# YOTSUBA_GNSS-receiver_Orion_ver_1_5_3.net
KiCad netlist of a schematic drawn in EAGLE
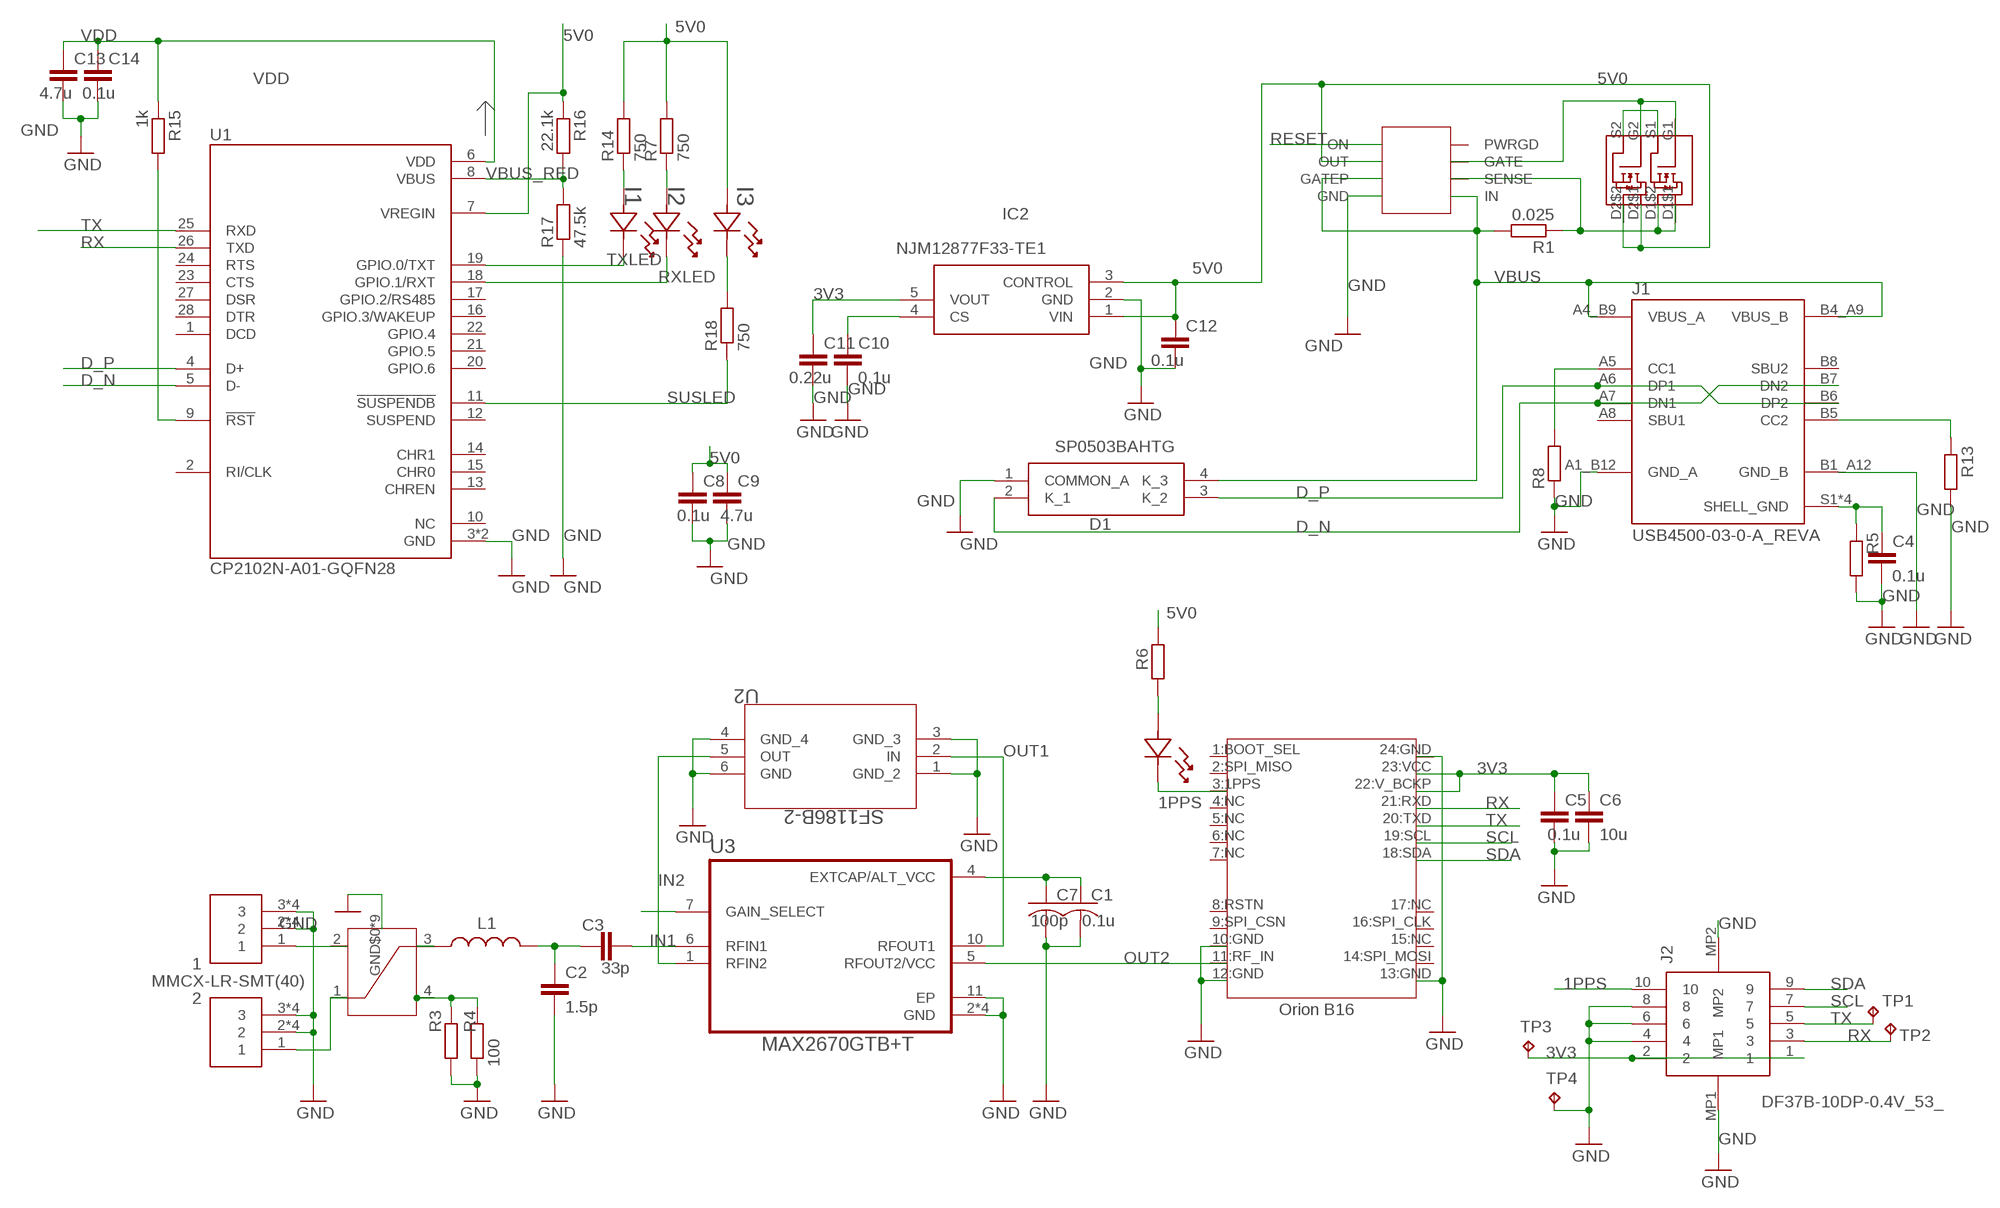
[diagram p0: schematic, sheet 1]

(export (version "E")
  (design (tool "Eeschema 10.0.6"))
  (components
    (comp (ref "1")
      (value "MMCX-LR-SMT(40)")
      (footprint "eagle-import:MMCX-LR-SMT(40)")
      (libsource (lib "eagle-import") (part "MMCX-LR-SMT(40)"))
    )
    (comp (ref "2")
      (value "MMCX-LR-SMT(40)")
      (footprint "eagle-import:MMCX-LR-SMT(40)")
      (libsource (lib "eagle-import") (part "MMCX-LR-SMT(40)"))
    )
    (comp (ref "C1")
      (value "0.1u")
      (footprint "eagle-import:C1608_OS")
      (libsource (lib "eagle-import") (part "C-US"))
    )
    (comp (ref "C2")
      (value "1.5p")
      (footprint "eagle-import:C1608")
      (libsource (lib "eagle-import") (part "C-EUC1608"))
    )
    (comp (ref "C3")
      (value "33p")
      (footprint "eagle-import:C1608")
      (libsource (lib "eagle-import") (part "C-EUC1608"))
    )
    (comp (ref "C4")
      (value "0.1u")
      (footprint "eagle-import:C1608")
      (libsource (lib "eagle-import") (part "C-EUC1608"))
    )
    (comp (ref "C5")
      (value "0.1u")
      (footprint "eagle-import:C1608")
      (libsource (lib "eagle-import") (part "C-EUC1608"))
    )
    (comp (ref "C6")
      (value "10u")
      (footprint "eagle-import:C1608")
      (libsource (lib "eagle-import") (part "C-EUC1608"))
    )
    (comp (ref "C7")
      (value "100p")
      (footprint "eagle-import:C1608_OS")
      (libsource (lib "eagle-import") (part "C-US"))
    )
    (comp (ref "C8")
      (value "0.1u")
      (footprint "eagle-import:C1608")
      (libsource (lib "eagle-import") (part "C-EUC1608"))
    )
    (comp (ref "C9")
      (value "4.7u")
      (footprint "eagle-import:C1608")
      (libsource (lib "eagle-import") (part "C-EUC1608"))
    )
    (comp (ref "C10")
      (value "0.1u")
      (footprint "eagle-import:C1608")
      (libsource (lib "eagle-import") (part "C-EUC1608"))
    )
    (comp (ref "C11")
      (value "0.22u")
      (footprint "eagle-import:C1608")
      (libsource (lib "eagle-import") (part "C-EUC1608"))
    )
    (comp (ref "C12")
      (value "0.1u")
      (footprint "eagle-import:C1608")
      (libsource (lib "eagle-import") (part "C-EUC1608"))
    )
    (comp (ref "C13")
      (value "4.7u")
      (footprint "eagle-import:C1608")
      (libsource (lib "eagle-import") (part "C-EUC1608"))
    )
    (comp (ref "C14")
      (value "0.1u")
      (footprint "eagle-import:C1608")
      (libsource (lib "eagle-import") (part "C-EUC1608"))
    )
    (comp (ref "D1")
      (value "SP0503BAHTG")
      (footprint "eagle-import:SP0503BAHTG")
      (fields (field (name "MOUSER_PART_NUMBER") "576-SP0503BAHTG"))
      (libsource (lib "eagle-import") (part "SP0503BAHTG"))
    )
    (comp (ref "I1")
      (value "SML-E12P8WT86")
      (footprint "eagle-import:LED_SMLD12_ROM")
      (fields (field (name "COPYRIGHT") "Copyright (C) 2023 Ultra Librarian. All rights reserved."))
      (libsource (lib "eagle-import") (part "SML-E12P8WT86"))
    )
    (comp (ref "I2")
      (value "SML-E12P8WT86")
      (footprint "eagle-import:LED_SMLD12_ROM")
      (fields (field (name "COPYRIGHT") "Copyright (C) 2023 Ultra Librarian. All rights reserved."))
      (libsource (lib "eagle-import") (part "SML-E12P8WT86"))
    )
    (comp (ref "I3")
      (value "SML-E12P8WT86")
      (footprint "eagle-import:LED_SMLD12_ROM")
      (fields (field (name "COPYRIGHT") "Copyright (C) 2023 Ultra Librarian. All rights reserved."))
      (libsource (lib "eagle-import") (part "SML-E12P8WT86"))
    )
    (comp (ref "IC2")
      (value "NJM12877F33-TE1")
      (footprint "eagle-import:SOT95P280X120-5N")
      (fields (field (name "MOUSER_PART_NUMBER") "513-NJM12877F33-TE1"))
      (libsource (lib "eagle-import") (part "NJM12877F33-TE1"))
    )
    (comp (ref "J1")
      (value "USB4500-03-0-A_REVA")
      (footprint "eagle-import:GCT_USB4500-03-0-A_REVA")
      (fields
        (field (name "DIGI-KEY_PART_NUMBER") "2073-USB4500-03-0-ATR-ND")
        (field (name "MF") "Global Connector Technology")
        (field (name "MP") "USB4500-03-0-A")
      )
      (libsource (lib "eagle-import") (part "USB4500-03-0-A_REVA"))
    )
    (comp (ref "J2")
      (value "DF37B-10DP-0.4V_53_")
      (footprint "eagle-import:DF37B10DP04V53")
      (fields
        (field (name "MANUFACTURER_PART_NUMBER") "DF37B-10DP-0.4V(53)")
        (field (name "MOUSER_PART_NUMBER") "798-DF37B10DP04V53")
      )
      (libsource (lib "eagle-import") (part "DF37B-10DP-0.4V_53_"))
    )
    (comp (ref "L1")
      (value "4.3n")
      (footprint "eagle-import:INDC1608X100N")
      (fields
        (field (name "DIGIKEY_PART_NUMBER") "490-6896-2-ND")
        (field (name "MF") "Murata")
        (field (name "MP") "LQW18AN4N3C00D")
      )
      (libsource (lib "eagle-import") (part "LQW18AN4N3C00D"))
    )
    (comp (ref "R1")
      (value "0.025")
      (footprint "eagle-import:R0603")
      (libsource (lib "eagle-import") (part "R-EU_R0603"))
    )
    (comp (ref "R3")
      (value "100")
      (footprint "eagle-import:R0603")
      (libsource (lib "eagle-import") (part "R-EU_R0603"))
    )
    (comp (ref "R4")
      (value "100")
      (footprint "eagle-import:R0603")
      (libsource (lib "eagle-import") (part "R-EU_R0603"))
    )
    (comp (ref "R5")
      (value "R-EU_R0603")
      (footprint "eagle-import:R0603")
      (libsource (lib "eagle-import") (part "R-EU_R0603"))
    )
    (comp (ref "R6")
      (value "R-EU_R0603")
      (footprint "eagle-import:R0603")
      (libsource (lib "eagle-import") (part "R-EU_R0603"))
    )
    (comp (ref "R7")
      (value "750")
      (footprint "eagle-import:R0603")
      (libsource (lib "eagle-import") (part "R-EU_R0603"))
    )
    (comp (ref "R8")
      (value "R-EU_R0603")
      (footprint "eagle-import:R0603")
      (libsource (lib "eagle-import") (part "R-EU_R0603"))
    )
    (comp (ref "R10")
      (value "SML-E12P8WT86")
      (footprint "eagle-import:LED_SMLD12_ROM")
      (fields (field (name "COPYRIGHT") "Copyright (C) 2023 Ultra Librarian. All rights reserved."))
      (libsource (lib "eagle-import") (part "SML-E12P8WT86"))
    )
    (comp (ref "R13")
      (value "R-EU_R0603")
      (footprint "eagle-import:R0603")
      (libsource (lib "eagle-import") (part "R-EU_R0603"))
    )
    (comp (ref "R14")
      (value "750")
      (footprint "eagle-import:R0603")
      (libsource (lib "eagle-import") (part "R-EU_R0603"))
    )
    (comp (ref "R15")
      (value "1k")
      (footprint "eagle-import:R0603")
      (libsource (lib "eagle-import") (part "R-EU_R0603"))
    )
    (comp (ref "R16")
      (value "22.1k")
      (footprint "eagle-import:R0603")
      (libsource (lib "eagle-import") (part "R-EU_R0603"))
    )
    (comp (ref "R17")
      (value "47.5k")
      (footprint "eagle-import:R0603")
      (libsource (lib "eagle-import") (part "R-EU_R0603"))
    )
    (comp (ref "R18")
      (value "750")
      (footprint "eagle-import:R0603")
      (libsource (lib "eagle-import") (part "R-EU_R0603"))
    )
    (comp (ref "TP1")
      (value "TPTP13SQ")
      (footprint "eagle-import:TP13SQ")
      (libsource (lib "eagle-import") (part "TPTP13SQ"))
    )
    (comp (ref "TP2")
      (value "TPTP13SQ")
      (footprint "eagle-import:TP13SQ")
      (libsource (lib "eagle-import") (part "TPTP13SQ"))
    )
    (comp (ref "TP3")
      (value "TPTP13SQ")
      (footprint "eagle-import:TP13SQ")
      (libsource (lib "eagle-import") (part "TPTP13SQ"))
    )
    (comp (ref "TP4")
      (value "TPTP13SQ")
      (footprint "eagle-import:TP13SQ")
      (libsource (lib "eagle-import") (part "TPTP13SQ"))
    )
    (comp (ref "U$1")
      (value "ORION_B16")
      (footprint "eagle-import:ORION_B16")
      (libsource (lib "eagle-import") (part "ORION_B16"))
    )
    (comp (ref "U$3")
      (value "HC125.A")
      (footprint "eagle-import:HC125.A")
      (libsource (lib "eagle-import") (part "HC125.A"))
    )
    (comp (ref "U$7")
      (value "DMG6898LSD")
      (footprint "eagle-import:SOIC127P600X150-8N")
      (libsource (lib "eagle-import") (part "DMG6898LSD"))
    )
    (comp (ref "U$8")
      (value "LTC4361")
      (footprint "eagle-import:SOP65P280X100-8N")
      (libsource (lib "eagle-import") (part "LTC4361"))
    )
    (comp (ref "U1")
      (value "CP2102N-A01-GQFN28")
      (footprint "eagle-import:QFN50P500X500X80-29N")
      (fields (field (name "MF") "Silicon Labs"))
      (libsource (lib "eagle-import") (part "CP2102N-A01-GQFN28"))
    )
    (comp (ref "U2")
      (value "SF1186B-2")
      (footprint "eagle-import:SM3030_MUR")
      (fields (field (name "COPYRIGHT") "Copyright (C) 2023 Ultra Librarian. All rights reserved."))
      (libsource (lib "eagle-import") (part "SF1186B-2"))
    )
    (comp (ref "U3")
      (value "MAX2670GTB+T")
      (footprint "eagle-import:DFN300X300X80-11N")
      (fields (field (name "MF") "Analog Devices"))
      (libsource (lib "eagle-import") (part "MAX2670GTB+T"))
    )
  )
  (nets
    (net (code "1") (name "/1PPS") (class "Default")
      (node (ref "J2") (pin "10") (pinfunction "10_10") (pintype "bidirectional"))
      (node (ref "R10") (pin "1") (pinfunction "1_1") (pintype "passive"))
      (node (ref "U$1") (pin "3:1PPS") (pinfunction "3:1PPS_3:1PPS") (pintype "bidirectional"))
    )
    (net (code "2") (name "/3V3") (class "Default")
      (node (ref "C11") (pin "1") (pinfunction "1_1") (pintype "passive"))
      (node (ref "C5") (pin "1") (pinfunction "1_1") (pintype "passive"))
      (node (ref "C6") (pin "1") (pinfunction "1_1") (pintype "passive"))
      (node (ref "IC2") (pin "5") (pinfunction "VOUT_5") (pintype "bidirectional"))
      (node (ref "J2") (pin "1") (pinfunction "1_1") (pintype "bidirectional"))
      (node (ref "J2") (pin "2") (pinfunction "2_2") (pintype "bidirectional"))
      (node (ref "TP3") (pin "TP") (pinfunction "TP_TP") (pintype "input"))
      (node (ref "U$1") (pin "22:V_BCKP") (pinfunction "22:V_BCKP_22:V_BCKP") (pintype "bidirectional"))
      (node (ref "U$1") (pin "23:VCC") (pinfunction "23:VCC_23:VCC") (pintype "bidirectional"))
    )
    (net (code "3") (name "/5V0") (class "Default")
      (node (ref "C12") (pin "1") (pinfunction "1_1") (pintype "passive"))
      (node (ref "C8") (pin "1") (pinfunction "1_1") (pintype "passive"))
      (node (ref "C9") (pin "1") (pinfunction "1_1") (pintype "passive"))
      (node (ref "I3") (pin "2") (pinfunction "2_2") (pintype "passive"))
      (node (ref "IC2") (pin "1") (pinfunction "VIN_1") (pintype "bidirectional"))
      (node (ref "IC2") (pin "3") (pinfunction "CONTROL_3") (pintype "bidirectional"))
      (node (ref "R14") (pin "2") (pinfunction "2_2") (pintype "passive"))
      (node (ref "R16") (pin "1") (pinfunction "1_1") (pintype "passive"))
      (node (ref "R6") (pin "2") (pinfunction "2_2") (pintype "passive"))
      (node (ref "R7") (pin "2") (pinfunction "2_2") (pintype "passive"))
      (node (ref "U$7") (pin "D2$1") (pinfunction "D2$1_D2$1") (pintype "bidirectional"))
      (node (ref "U$7") (pin "D2$2") (pinfunction "D2$2_D2$2") (pintype "bidirectional"))
      (node (ref "U$8") (pin "OUT") (pinfunction "OUT_OUT") (pintype "bidirectional"))
      (node (ref "U1") (pin "7") (pinfunction "VREGIN_7") (pintype "power_in"))
    )
    (net (code "4") (name "/D_N") (class "Default")
      (node (ref "D1") (pin "2") (pinfunction "K_1_2") (pintype "bidirectional"))
      (node (ref "J1") (pin "A7") (pinfunction "DN1_A7") (pintype "bidirectional"))
      (node (ref "J1") (pin "B7") (pinfunction "DN2_B7") (pintype "bidirectional"))
      (node (ref "U1") (pin "5") (pinfunction "D-_5") (pintype "bidirectional"))
    )
    (net (code "5") (name "/D_P") (class "Default")
      (node (ref "D1") (pin "3") (pinfunction "K_2_3") (pintype "bidirectional"))
      (node (ref "J1") (pin "A6") (pinfunction "DP1_A6") (pintype "bidirectional"))
      (node (ref "J1") (pin "B6") (pinfunction "DP2_B6") (pintype "bidirectional"))
      (node (ref "U1") (pin "4") (pinfunction "D+_4") (pintype "bidirectional"))
    )
    (net (code "6") (name "/IN1") (class "Default")
      (node (ref "C3") (pin "2") (pinfunction "2_2") (pintype "passive"))
      (node (ref "U3") (pin "6") (pinfunction "RFIN1_6") (pintype "input"))
    )
    (net (code "7") (name "/IN2") (class "Default")
      (node (ref "U2") (pin "5") (pinfunction "OUT_5") (pintype "output"))
      (node (ref "U3") (pin "1") (pinfunction "RFIN2_1") (pintype "input"))
    )
    (net (code "8") (name "/OUT1") (class "Default")
      (node (ref "U2") (pin "2") (pinfunction "IN_2") (pintype "input"))
      (node (ref "U3") (pin "10") (pinfunction "RFOUT1_10") (pintype "output"))
    )
    (net (code "9") (name "/OUT2") (class "Default")
      (node (ref "U$1") (pin "11:RF_IN") (pinfunction "11:RF_IN_11:RF_IN") (pintype "bidirectional"))
      (node (ref "U3") (pin "5") (pinfunction "RFOUT2/VCC_5") (pintype "output"))
    )
    (net (code "10") (name "/RESET") (class "Default")
      (node (ref "U$8") (pin "ON") (pinfunction "ON_ON") (pintype "bidirectional"))
    )
    (net (code "11") (name "/RX") (class "Default")
      (node (ref "J2") (pin "3") (pinfunction "3_3") (pintype "bidirectional"))
      (node (ref "TP2") (pin "TP") (pinfunction "TP_TP") (pintype "input"))
      (node (ref "U$1") (pin "21:RXD") (pinfunction "21:RXD_21:RXD") (pintype "bidirectional"))
      (node (ref "U1") (pin "26") (pinfunction "TXD_26") (pintype "output"))
    )
    (net (code "12") (name "/RXLED") (class "Default")
      (node (ref "I2") (pin "1") (pinfunction "1_1") (pintype "passive"))
      (node (ref "U1") (pin "18") (pinfunction "GPIO.1/RXT_18") (pintype "bidirectional"))
    )
    (net (code "13") (name "/SCL") (class "Default")
      (node (ref "J2") (pin "7") (pinfunction "7_7") (pintype "bidirectional"))
      (node (ref "U$1") (pin "19:SCL") (pinfunction "19:SCL_19:SCL") (pintype "bidirectional"))
    )
    (net (code "14") (name "/SDA") (class "Default")
      (node (ref "J2") (pin "9") (pinfunction "9_9") (pintype "bidirectional"))
      (node (ref "U$1") (pin "18:SDA") (pinfunction "18:SDA_18:SDA") (pintype "bidirectional"))
    )
    (net (code "15") (name "/SUSLED") (class "Default")
      (node (ref "R18") (pin "1") (pinfunction "1_1") (pintype "passive"))
      (node (ref "U1") (pin "11") (pinfunction "~{SUSPENDB}_11") (pintype "output"))
    )
    (net (code "16") (name "/TX") (class "Default")
      (node (ref "J2") (pin "5") (pinfunction "5_5") (pintype "bidirectional"))
      (node (ref "TP1") (pin "TP") (pinfunction "TP_TP") (pintype "input"))
      (node (ref "U$1") (pin "20:TXD") (pinfunction "20:TXD_20:TXD") (pintype "bidirectional"))
      (node (ref "U1") (pin "25") (pinfunction "RXD_25") (pintype "input"))
    )
    (net (code "17") (name "/TXLED") (class "Default")
      (node (ref "I1") (pin "1") (pinfunction "1_1") (pintype "passive"))
      (node (ref "U1") (pin "19") (pinfunction "GPIO.0/TXT_19") (pintype "bidirectional"))
    )
    (net (code "18") (name "/VBUS") (class "Default")
      (node (ref "D1") (pin "4") (pinfunction "K_3_4") (pintype "bidirectional"))
      (node (ref "J1") (pin "A4_B9") (pinfunction "VBUS_A_A4_B9") (pintype "power_in"))
      (node (ref "J1") (pin "B4_A9") (pinfunction "VBUS_B_B4_A9") (pintype "power_in"))
      (node (ref "R1") (pin "2") (pinfunction "2_2") (pintype "passive"))
      (node (ref "U$8") (pin "GATEP") (pinfunction "GATEP_GATEP") (pintype "bidirectional"))
      (node (ref "U$8") (pin "IN") (pinfunction "IN_IN") (pintype "bidirectional"))
    )
    (net (code "19") (name "/VBUS_RED") (class "Default")
      (node (ref "R16") (pin "2") (pinfunction "2_2") (pintype "passive"))
      (node (ref "R17") (pin "2") (pinfunction "2_2") (pintype "passive"))
      (node (ref "U1") (pin "8") (pinfunction "VBUS_8") (pintype "power_in"))
    )
    (net (code "20") (name "/VDD") (class "Default")
      (node (ref "C13") (pin "1") (pinfunction "1_1") (pintype "passive"))
      (node (ref "C14") (pin "1") (pinfunction "1_1") (pintype "passive"))
      (node (ref "R15") (pin "1") (pinfunction "1_1") (pintype "passive"))
      (node (ref "U1") (pin "6") (pinfunction "VDD_6") (pintype "power_in"))
    )
    (net (code "21") (name "GND") (class "Default")
      (node (ref "1") (pin "2") (pinfunction "2_2") (pintype "bidirectional"))
      (node (ref "1") (pin "3") (pinfunction "3_3") (pintype "bidirectional"))
      (node (ref "1") (pin "4") (pinfunction "2_4") (pintype "bidirectional"))
      (node (ref "1") (pin "5") (pinfunction "3_5") (pintype "bidirectional"))
      (node (ref "1") (pin "P$1") (pinfunction "2_P$1") (pintype "bidirectional"))
      (node (ref "1") (pin "P$2") (pinfunction "2_P$2") (pintype "bidirectional"))
      (node (ref "1") (pin "P$3") (pinfunction "3_P$3") (pintype "bidirectional"))
      (node (ref "1") (pin "P$4") (pinfunction "3_P$4") (pintype "bidirectional"))
      (node (ref "2") (pin "2") (pinfunction "2_2") (pintype "bidirectional"))
      (node (ref "2") (pin "3") (pinfunction "3_3") (pintype "bidirectional"))
      (node (ref "2") (pin "4") (pinfunction "2_4") (pintype "bidirectional"))
      (node (ref "2") (pin "5") (pinfunction "3_5") (pintype "bidirectional"))
      (node (ref "2") (pin "P$1") (pinfunction "2_P$1") (pintype "bidirectional"))
      (node (ref "2") (pin "P$2") (pinfunction "2_P$2") (pintype "bidirectional"))
      (node (ref "2") (pin "P$3") (pinfunction "3_P$3") (pintype "bidirectional"))
      (node (ref "2") (pin "P$4") (pinfunction "3_P$4") (pintype "bidirectional"))
      (node (ref "C1") (pin "2") (pinfunction "2_2") (pintype "passive"))
      (node (ref "C10") (pin "2") (pinfunction "2_2") (pintype "passive"))
      (node (ref "C11") (pin "2") (pinfunction "2_2") (pintype "passive"))
      (node (ref "C12") (pin "2") (pinfunction "2_2") (pintype "passive"))
      (node (ref "C13") (pin "2") (pinfunction "2_2") (pintype "passive"))
      (node (ref "C14") (pin "2") (pinfunction "2_2") (pintype "passive"))
      (node (ref "C2") (pin "2") (pinfunction "2_2") (pintype "passive"))
      (node (ref "C4") (pin "2") (pinfunction "2_2") (pintype "passive"))
      (node (ref "C5") (pin "2") (pinfunction "2_2") (pintype "passive"))
      (node (ref "C6") (pin "2") (pinfunction "2_2") (pintype "passive"))
      (node (ref "C7") (pin "2") (pinfunction "2_2") (pintype "passive"))
      (node (ref "C8") (pin "2") (pinfunction "2_2") (pintype "passive"))
      (node (ref "C9") (pin "2") (pinfunction "2_2") (pintype "passive"))
      (node (ref "D1") (pin "1") (pinfunction "COMMON_A_1") (pintype "bidirectional"))
      (node (ref "IC2") (pin "2") (pinfunction "GND_2") (pintype "bidirectional"))
      (node (ref "J1") (pin "A1_B12") (pinfunction "GND_A_A1_B12") (pintype "power_in"))
      (node (ref "J1") (pin "B1_A12") (pinfunction "GND_B_B1_A12") (pintype "power_in"))
      (node (ref "J2") (pin "4") (pinfunction "4_4") (pintype "bidirectional"))
      (node (ref "J2") (pin "6") (pinfunction "6_6") (pintype "bidirectional"))
      (node (ref "J2") (pin "8") (pinfunction "8_8") (pintype "bidirectional"))
      (node (ref "J2") (pin "MP1") (pinfunction "MP1_MP1") (pintype "bidirectional"))
      (node (ref "J2") (pin "MP2") (pinfunction "MP2_MP2") (pintype "bidirectional"))
      (node (ref "R13") (pin "2") (pinfunction "2_2") (pintype "passive"))
      (node (ref "R17") (pin "1") (pinfunction "1_1") (pintype "passive"))
      (node (ref "R3") (pin "1") (pinfunction "1_1") (pintype "passive"))
      (node (ref "R4") (pin "1") (pinfunction "1_1") (pintype "passive"))
      (node (ref "R5") (pin "2") (pinfunction "2_2") (pintype "passive"))
      (node (ref "R8") (pin "1") (pinfunction "1_1") (pintype "passive"))
      (node (ref "TP4") (pin "TP") (pinfunction "TP_TP") (pintype "input"))
      (node (ref "U$1") (pin "10:GND") (pinfunction "10:GND_10:GND") (pintype "bidirectional"))
      (node (ref "U$1") (pin "12:GND") (pinfunction "12:GND_12:GND") (pintype "bidirectional"))
      (node (ref "U$1") (pin "13:GND") (pinfunction "13:GND_13:GND") (pintype "bidirectional"))
      (node (ref "U$1") (pin "24:GND") (pinfunction "24:GND_24:GND") (pintype "bidirectional"))
      (node (ref "U$3") (pin "GND$0") (pinfunction "GND_GND$0") (pintype "bidirectional"))
      (node (ref "U$3") (pin "GND$1") (pinfunction "GND_GND$1") (pintype "bidirectional"))
      (node (ref "U$3") (pin "GND$2") (pinfunction "GND_GND$2") (pintype "bidirectional"))
      (node (ref "U$3") (pin "GND$3") (pinfunction "GND_GND$3") (pintype "bidirectional"))
      (node (ref "U$3") (pin "GND$4") (pinfunction "GND_GND$4") (pintype "bidirectional"))
      (node (ref "U$3") (pin "GND$5") (pinfunction "GND_GND$5") (pintype "bidirectional"))
      (node (ref "U$3") (pin "GND$6") (pinfunction "GND_GND$6") (pintype "bidirectional"))
      (node (ref "U$3") (pin "GND$7") (pinfunction "GND_GND$7") (pintype "bidirectional"))
      (node (ref "U$3") (pin "GND$8") (pinfunction "GND_GND$8") (pintype "bidirectional"))
      (node (ref "U$8") (pin "GND") (pinfunction "GND_GND") (pintype "bidirectional"))
      (node (ref "U1") (pin "29") (pinfunction "GND_29") (pintype "power_in"))
      (node (ref "U1") (pin "3") (pinfunction "GND_3") (pintype "power_in"))
      (node (ref "U2") (pin "1") (pinfunction "GND_2_1") (pintype "passive"))
      (node (ref "U2") (pin "3") (pinfunction "GND_3_3") (pintype "passive"))
      (node (ref "U2") (pin "4") (pinfunction "GND_4_4") (pintype "passive"))
      (node (ref "U2") (pin "6") (pinfunction "GND_6") (pintype "passive"))
      (node (ref "U3") (pin "11") (pinfunction "EP_11") (pintype "power_in"))
      (node (ref "U3") (pin "2") (pinfunction "GND_2") (pintype "power_in"))
      (node (ref "U3") (pin "3") (pinfunction "GND_3") (pintype "power_in"))
      (node (ref "U3") (pin "8") (pinfunction "GND_8") (pintype "power_in"))
      (node (ref "U3") (pin "9") (pinfunction "GND_9") (pintype "power_in"))
    )
    (net (code "22") (name "Net-(1-Pad1)") (class "Default")
      (node (ref "1") (pin "1") (pinfunction "1_1") (pintype "bidirectional"))
      (node (ref "U$3") (pin "2") (pinfunction "2_2") (pintype "bidirectional"))
    )
    (net (code "23") (name "Net-(2-Pad1)") (class "Default")
      (node (ref "2") (pin "1") (pinfunction "1_1") (pintype "bidirectional"))
      (node (ref "U$3") (pin "1") (pinfunction "1_1") (pintype "bidirectional"))
    )
    (net (code "24") (name "Net-(C2-Pad1)") (class "Default")
      (node (ref "C2") (pin "1") (pinfunction "1_1") (pintype "passive"))
      (node (ref "C3") (pin "1") (pinfunction "1_1") (pintype "passive"))
      (node (ref "L1") (pin "2") (pinfunction "2_2") (pintype "passive"))
    )
    (net (code "25") (name "Net-(C4-Pad1)") (class "Default")
      (node (ref "C4") (pin "1") (pinfunction "1_1") (pintype "passive"))
      (node (ref "J1") (pin "S1") (pinfunction "SHELL_GND_S1") (pintype "power_in"))
      (node (ref "J1") (pin "S2") (pinfunction "SHELL_GND_S2") (pintype "power_in"))
      (node (ref "J1") (pin "S3") (pinfunction "SHELL_GND_S3") (pintype "power_in"))
      (node (ref "J1") (pin "S4") (pinfunction "SHELL_GND_S4") (pintype "power_in"))
      (node (ref "R5") (pin "1") (pinfunction "1_1") (pintype "passive"))
    )
    (net (code "26") (name "Net-(I1-Pad2)") (class "Default")
      (node (ref "I1") (pin "2") (pinfunction "2_2") (pintype "passive"))
      (node (ref "R14") (pin "1") (pinfunction "1_1") (pintype "passive"))
    )
    (net (code "27") (name "Net-(I2-Pad2)") (class "Default")
      (node (ref "I2") (pin "2") (pinfunction "2_2") (pintype "passive"))
      (node (ref "R7") (pin "1") (pinfunction "1_1") (pintype "passive"))
    )
    (net (code "28") (name "Net-(I3-Pad1)") (class "Default")
      (node (ref "I3") (pin "1") (pinfunction "1_1") (pintype "passive"))
      (node (ref "R18") (pin "2") (pinfunction "2_2") (pintype "passive"))
    )
    (net (code "29") (name "Net-(IC2-CS)") (class "Default")
      (node (ref "C10") (pin "1") (pinfunction "1_1") (pintype "passive"))
      (node (ref "IC2") (pin "4") (pinfunction "CS_4") (pintype "bidirectional"))
    )
    (net (code "30") (name "Net-(J1-CC1)") (class "Default")
      (node (ref "J1") (pin "A5") (pinfunction "CC1_A5") (pintype "bidirectional"))
      (node (ref "R8") (pin "2") (pinfunction "2_2") (pintype "passive"))
    )
    (net (code "31") (name "Net-(J1-CC2)") (class "Default")
      (node (ref "J1") (pin "B5") (pinfunction "CC2_B5") (pintype "bidirectional"))
      (node (ref "R13") (pin "1") (pinfunction "1_1") (pintype "passive"))
    )
    (net (code "32") (name "Net-(L1-Pad1)") (class "Default")
      (node (ref "L1") (pin "1") (pinfunction "1_1") (pintype "passive"))
      (node (ref "U$3") (pin "3") (pinfunction "3_3") (pintype "bidirectional"))
    )
    (net (code "33") (name "Net-(R1-Pad1)") (class "Default")
      (node (ref "R1") (pin "1") (pinfunction "1_1") (pintype "passive"))
      (node (ref "U$7") (pin "D1$1") (pinfunction "D1$1_D1$1") (pintype "bidirectional"))
      (node (ref "U$7") (pin "D1$2") (pinfunction "D1$2_D1$2") (pintype "bidirectional"))
      (node (ref "U$8") (pin "SENSE") (pinfunction "SENSE_SENSE") (pintype "bidirectional"))
    )
    (net (code "34") (name "Net-(R3-Pad2)") (class "Default")
      (node (ref "R3") (pin "2") (pinfunction "2_2") (pintype "passive"))
      (node (ref "R4") (pin "2") (pinfunction "2_2") (pintype "passive"))
      (node (ref "U$3") (pin "4") (pinfunction "4_4") (pintype "bidirectional"))
    )
    (net (code "35") (name "Net-(R10-Pad2)") (class "Default")
      (node (ref "R10") (pin "2") (pinfunction "2_2") (pintype "passive"))
      (node (ref "R6") (pin "1") (pinfunction "1_1") (pintype "passive"))
    )
    (net (code "36") (name "Net-(U$7-PadG1)") (class "Default")
      (node (ref "U$7") (pin "G1") (pinfunction "G1_G1") (pintype "bidirectional"))
      (node (ref "U$7") (pin "G2") (pinfunction "G2_G2") (pintype "bidirectional"))
      (node (ref "U$8") (pin "GATE") (pinfunction "GATE_GATE") (pintype "bidirectional"))
    )
    (net (code "37") (name "Net-(U$7-PadS1)") (class "Default")
      (node (ref "U$7") (pin "S1") (pinfunction "S1_S1") (pintype "bidirectional"))
      (node (ref "U$7") (pin "S2") (pinfunction "S2_S2") (pintype "bidirectional"))
    )
    (net (code "38") (name "Net-(U1-~{RST})") (class "Default")
      (node (ref "R15") (pin "2") (pinfunction "2_2") (pintype "passive"))
      (node (ref "U1") (pin "9") (pinfunction "~{RST}_9") (pintype "input"))
    )
    (net (code "39") (name "Net-(U3-EXTCAP{slash}ALT_VCC)") (class "Default")
      (node (ref "C1") (pin "1") (pinfunction "1_1") (pintype "passive"))
      (node (ref "C7") (pin "1") (pinfunction "1_1") (pintype "passive"))
      (node (ref "U3") (pin "4") (pinfunction "EXTCAP/ALT_VCC_4") (pintype "power_in"))
    )
    (net (code "40") (name "unconnected-(J1-SBU1-PadA8)") (class "Default")
      (node (ref "J1") (pin "A8") (pinfunction "SBU1_A8") (pintype "bidirectional"))
    )
    (net (code "41") (name "unconnected-(J1-SBU2-PadB8)") (class "Default")
      (node (ref "J1") (pin "B8") (pinfunction "SBU2_B8") (pintype "bidirectional"))
    )
    (net (code "42") (name "unconnected-(U$1-Pad1:BOOT_SEL)") (class "Default")
      (node (ref "U$1") (pin "1:BOOT_SEL") (pinfunction "1:BOOT_SEL_1:BOOT_SEL") (pintype "bidirectional"))
    )
    (net (code "43") (name "unconnected-(U$1-Pad2:SPI_MISO)") (class "Default")
      (node (ref "U$1") (pin "2:SPI_MISO") (pinfunction "2:SPI_MISO_2:SPI_MISO") (pintype "bidirectional"))
    )
    (net (code "44") (name "unconnected-(U$1-Pad4:NC)") (class "Default")
      (node (ref "U$1") (pin "4:NC") (pinfunction "4:NC_4:NC") (pintype "bidirectional"))
    )
    (net (code "45") (name "unconnected-(U$1-Pad5:NC)") (class "Default")
      (node (ref "U$1") (pin "5:NC") (pinfunction "5:NC_5:NC") (pintype "bidirectional"))
    )
    (net (code "46") (name "unconnected-(U$1-Pad6:NC)") (class "Default")
      (node (ref "U$1") (pin "6:NC") (pinfunction "6:NC_6:NC") (pintype "bidirectional"))
    )
    (net (code "47") (name "unconnected-(U$1-Pad7:NC)") (class "Default")
      (node (ref "U$1") (pin "7:NC") (pinfunction "7:NC_7:NC") (pintype "bidirectional"))
    )
    (net (code "48") (name "unconnected-(U$1-Pad8:RSTN)") (class "Default")
      (node (ref "U$1") (pin "8:RSTN") (pinfunction "8:RSTN_8:RSTN") (pintype "bidirectional"))
    )
    (net (code "49") (name "unconnected-(U$1-Pad9:SPI_CSN)") (class "Default")
      (node (ref "U$1") (pin "9:SPI_CSN") (pinfunction "9:SPI_CSN_9:SPI_CSN") (pintype "bidirectional"))
    )
    (net (code "50") (name "unconnected-(U$1-Pad14:SPI_MOSI)") (class "Default")
      (node (ref "U$1") (pin "14:SPI_MOSI") (pinfunction "14:SPI_MOSI_14:SPI_MOSI") (pintype "bidirectional"))
    )
    (net (code "51") (name "unconnected-(U$1-Pad15:NC)") (class "Default")
      (node (ref "U$1") (pin "15:NC") (pinfunction "15:NC_15:NC") (pintype "bidirectional"))
    )
    (net (code "52") (name "unconnected-(U$1-Pad16:SPI_CLK)") (class "Default")
      (node (ref "U$1") (pin "16:SPI_CLK") (pinfunction "16:SPI_CLK_16:SPI_CLK") (pintype "bidirectional"))
    )
    (net (code "53") (name "unconnected-(U$1-Pad17:NC)") (class "Default")
      (node (ref "U$1") (pin "17:NC") (pinfunction "17:NC_17:NC") (pintype "bidirectional"))
    )
    (net (code "54") (name "unconnected-(U$8-PadPWRGD)") (class "Default")
      (node (ref "U$8") (pin "PWRGD") (pinfunction "PWRGD_PWRGD") (pintype "bidirectional"))
    )
    (net (code "55") (name "unconnected-(U1-CHR0-Pad15)") (class "Default")
      (node (ref "U1") (pin "15") (pinfunction "CHR0_15") (pintype "output"))
    )
    (net (code "56") (name "unconnected-(U1-CHR1-Pad14)") (class "Default")
      (node (ref "U1") (pin "14") (pinfunction "CHR1_14") (pintype "output"))
    )
    (net (code "57") (name "unconnected-(U1-CHREN-Pad13)") (class "Default")
      (node (ref "U1") (pin "13") (pinfunction "CHREN_13") (pintype "output"))
    )
    (net (code "58") (name "unconnected-(U1-CTS-Pad23)") (class "Default")
      (node (ref "U1") (pin "23") (pinfunction "CTS_23") (pintype "input"))
    )
    (net (code "59") (name "unconnected-(U1-DCD-Pad1)") (class "Default")
      (node (ref "U1") (pin "1") (pinfunction "DCD_1") (pintype "input"))
    )
    (net (code "60") (name "unconnected-(U1-DSR-Pad27)") (class "Default")
      (node (ref "U1") (pin "27") (pinfunction "DSR_27") (pintype "input"))
    )
    (net (code "61") (name "unconnected-(U1-DTR-Pad28)") (class "Default")
      (node (ref "U1") (pin "28") (pinfunction "DTR_28") (pintype "output"))
    )
    (net (code "62") (name "unconnected-(U1-GPIO.2{slash}RS485-Pad17)") (class "Default")
      (node (ref "U1") (pin "17") (pinfunction "GPIO.2/RS485_17") (pintype "bidirectional"))
    )
    (net (code "63") (name "unconnected-(U1-GPIO.3{slash}WAKEUP-Pad16)") (class "Default")
      (node (ref "U1") (pin "16") (pinfunction "GPIO.3/WAKEUP_16") (pintype "bidirectional"))
    )
    (net (code "64") (name "unconnected-(U1-GPIO.4-Pad22)") (class "Default")
      (node (ref "U1") (pin "22") (pinfunction "GPIO.4_22") (pintype "bidirectional"))
    )
    (net (code "65") (name "unconnected-(U1-GPIO.5-Pad21)") (class "Default")
      (node (ref "U1") (pin "21") (pinfunction "GPIO.5_21") (pintype "bidirectional"))
    )
    (net (code "66") (name "unconnected-(U1-GPIO.6-Pad20)") (class "Default")
      (node (ref "U1") (pin "20") (pinfunction "GPIO.6_20") (pintype "bidirectional"))
    )
    (net (code "67") (name "unconnected-(U1-NC-Pad10)") (class "Default")
      (node (ref "U1") (pin "10") (pinfunction "NC_10") (pintype "no_connect"))
    )
    (net (code "68") (name "unconnected-(U1-RI{slash}CLK-Pad2)") (class "Default")
      (node (ref "U1") (pin "2") (pinfunction "RI/CLK_2") (pintype "bidirectional"))
    )
    (net (code "69") (name "unconnected-(U1-RTS-Pad24)") (class "Default")
      (node (ref "U1") (pin "24") (pinfunction "RTS_24") (pintype "output"))
    )
    (net (code "70") (name "unconnected-(U1-SUSPEND-Pad12)") (class "Default")
      (node (ref "U1") (pin "12") (pinfunction "SUSPEND_12") (pintype "output"))
    )
    (net (code "71") (name "unconnected-(U3-GAIN_SELECT-Pad7)") (class "Default")
      (node (ref "U3") (pin "7") (pinfunction "GAIN_SELECT_7") (pintype "input"))
    )
  )
)
